# 2HE2E_Tester.net
KiCad netlist of a schematic drawn in Altium Designer
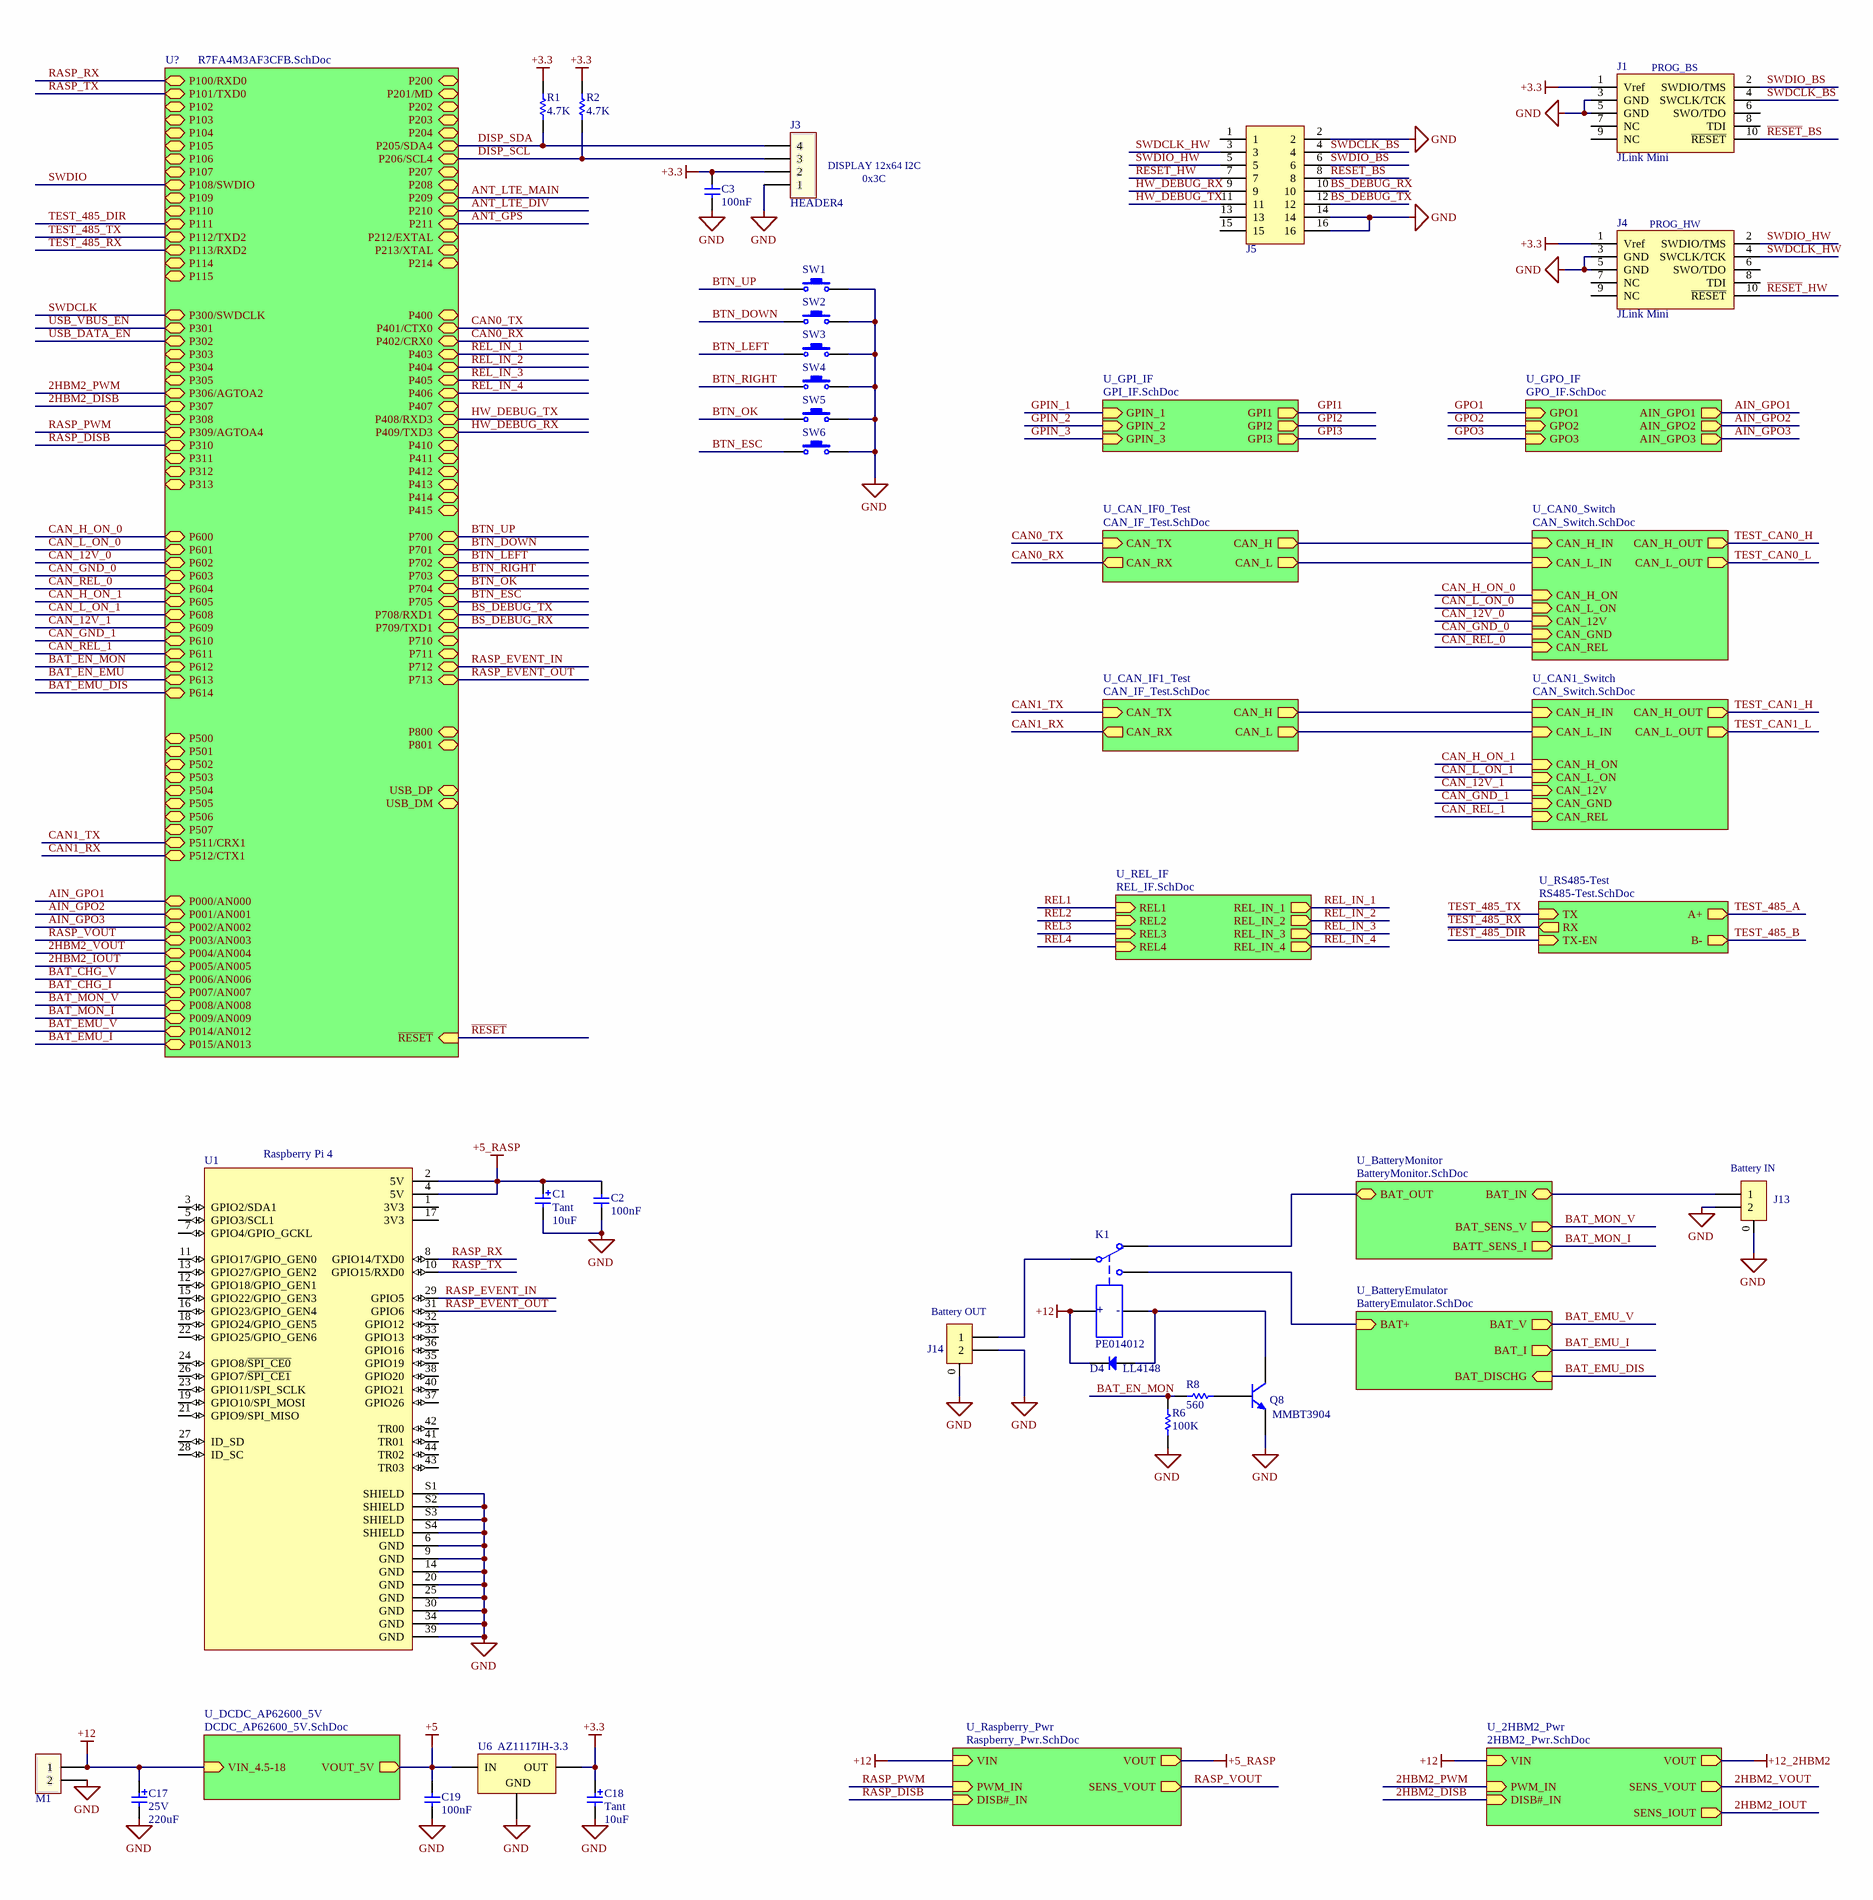
[diagram p0: 2HE2E_Tester.SchDoc, left]
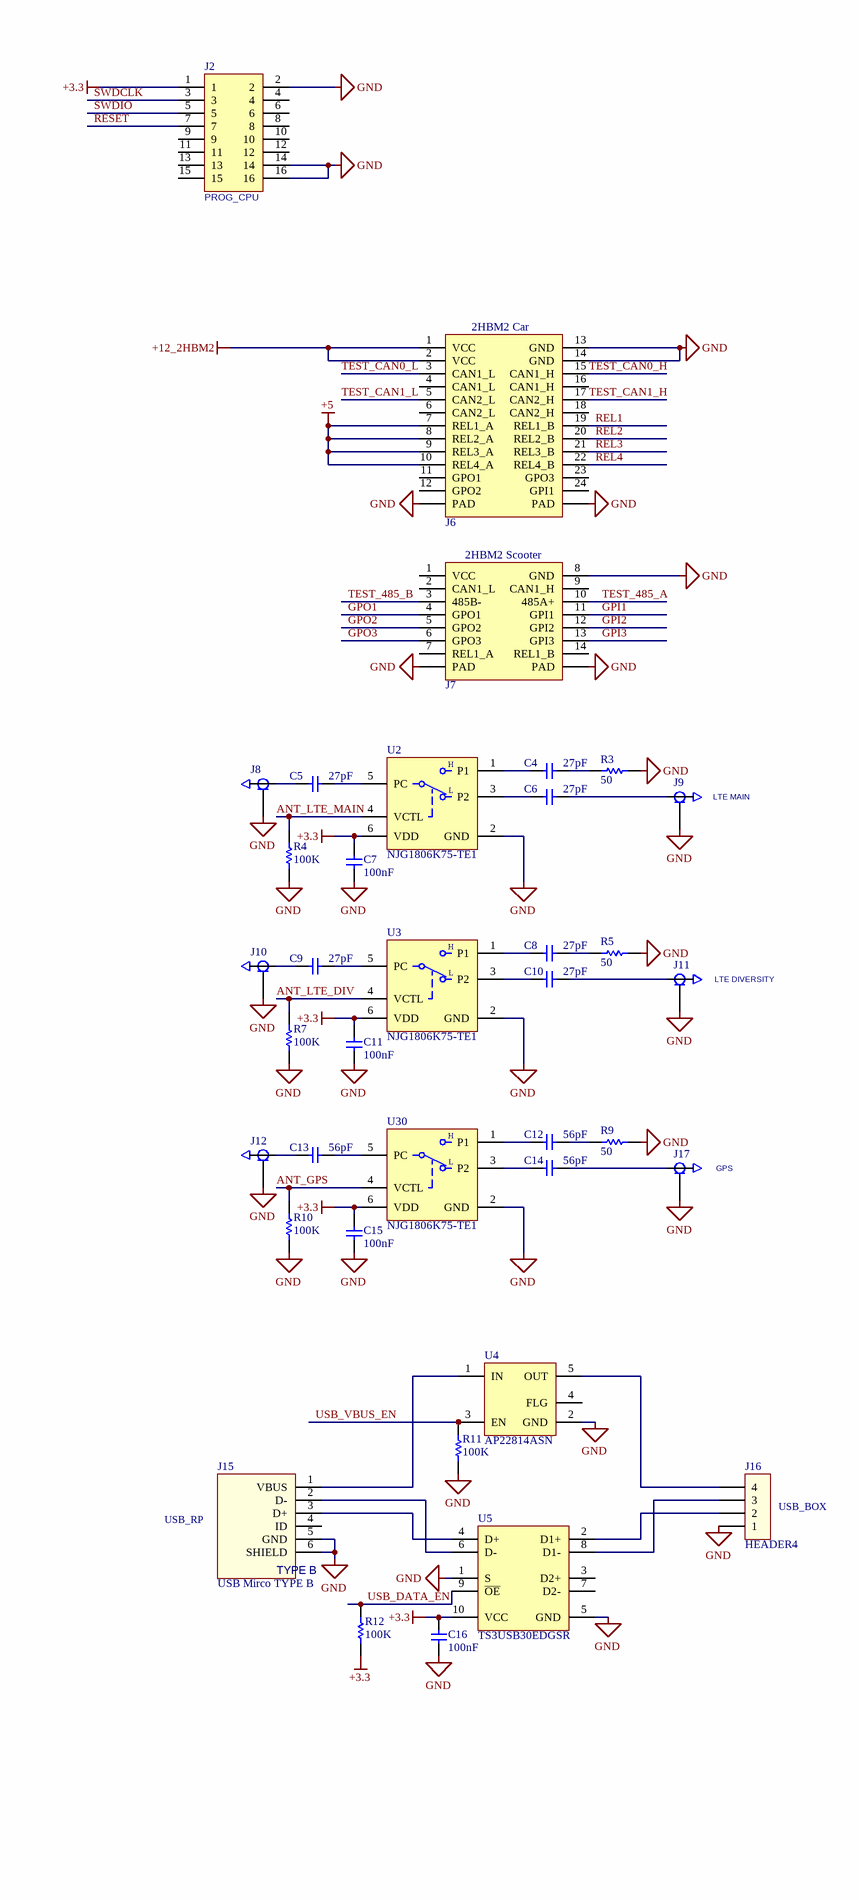
[diagram p1: 2HE2E_Tester.SchDoc, right]

(export (version "E")
  (design (tool "Eeschema 10.0.6"))
  (components
    (comp (ref "C1")
      (value "Tant")
      (footprint "Cap CASE B")
      (description "Capacitor tantalio SMD")
      (fields (field (name "ALTIUM_VALUE") "10uF"))
      (libsource (lib "Plume") (part "Cap Tantalio"))
    )
    (comp (ref "C2")
      (value "100nF")
      (footprint "0603M-C")
      (description "Ceramic Capacitor")
      (fields (field (name "Comment") "Cap Ceramic"))
      (libsource (lib "Plume") (part "Cap Ceramic"))
    )
    (comp (ref "C3")
      (value "100nF")
      (footprint "0603M-C")
      (description "Ceramic Capacitor")
      (fields (field (name "Comment") "Cap Ceramic"))
      (libsource (lib "Plume") (part "Cap Ceramic"))
    )
    (comp (ref "C4")
      (value "27pF")
      (footprint "0402M-C")
      (description "Ceramic Capacitor")
      (fields (field (name "Comment") "Cap Ceramic"))
      (libsource (lib "Plume") (part "Cap Ceramic"))
    )
    (comp (ref "C5")
      (value "27pF")
      (footprint "0402M-C")
      (description "Ceramic Capacitor")
      (fields (field (name "Comment") "Cap Ceramic"))
      (libsource (lib "Plume") (part "Cap Ceramic"))
    )
    (comp (ref "C6")
      (value "27pF")
      (footprint "0402M-C")
      (description "Ceramic Capacitor")
      (fields (field (name "Comment") "Cap Ceramic"))
      (libsource (lib "Plume") (part "Cap Ceramic"))
    )
    (comp (ref "C7")
      (value "100nF")
      (footprint "0603M-C")
      (description "Ceramic Capacitor")
      (fields (field (name "Comment") "Cap Ceramic"))
      (libsource (lib "Plume") (part "Cap Ceramic"))
    )
    (comp (ref "C8")
      (value "27pF")
      (footprint "0402M-C")
      (description "Ceramic Capacitor")
      (fields (field (name "Comment") "Cap Ceramic"))
      (libsource (lib "Plume") (part "Cap Ceramic"))
    )
    (comp (ref "C9")
      (value "27pF")
      (footprint "0402M-C")
      (description "Ceramic Capacitor")
      (fields (field (name "Comment") "Cap Ceramic"))
      (libsource (lib "Plume") (part "Cap Ceramic"))
    )
    (comp (ref "C10")
      (value "27pF")
      (footprint "0402M-C")
      (description "Ceramic Capacitor")
      (fields (field (name "Comment") "Cap Ceramic"))
      (libsource (lib "Plume") (part "Cap Ceramic"))
    )
    (comp (ref "C11")
      (value "100nF")
      (footprint "0603M-C")
      (description "Ceramic Capacitor")
      (fields (field (name "Comment") "Cap Ceramic"))
      (libsource (lib "Plume") (part "Cap Ceramic"))
    )
    (comp (ref "C12")
      (value "56pF")
      (footprint "0402M-C")
      (description "Ceramic Capacitor")
      (fields (field (name "Comment") "Cap Ceramic"))
      (libsource (lib "Plume") (part "Cap Ceramic"))
    )
    (comp (ref "C13")
      (value "56pF")
      (footprint "0402M-C")
      (description "Ceramic Capacitor")
      (fields (field (name "Comment") "Cap Ceramic"))
      (libsource (lib "Plume") (part "Cap Ceramic"))
    )
    (comp (ref "C14")
      (value "56pF")
      (footprint "0402M-C")
      (description "Ceramic Capacitor")
      (fields (field (name "Comment") "Cap Ceramic"))
      (libsource (lib "Plume") (part "Cap Ceramic"))
    )
    (comp (ref "C15")
      (value "100nF")
      (footprint "0603M-C")
      (description "Ceramic Capacitor")
      (fields (field (name "Comment") "Cap Ceramic"))
      (libsource (lib "Plume") (part "Cap Ceramic"))
    )
    (comp (ref "C16")
      (value "100nF")
      (footprint "0603M-C")
      (description "Ceramic Capacitor")
      (fields (field (name "Comment") "Cap Ceramic"))
      (libsource (lib "Plume") (part "Cap Ceramic"))
    )
    (comp (ref "C17")
      (value "25V")
      (footprint "Cap Elet SMD 8.0 mm CASE F-H10.5mm")
      (description "Condensatore elettrolitico")
      (fields (field (name "ALTIUM_VALUE") "220uF"))
      (libsource (lib "Plume") (part "Cap Elettrolitico"))
    )
    (comp (ref "C18")
      (value "Tant")
      (footprint "Cap CASE B")
      (description "Capacitor tantalio SMD")
      (fields (field (name "ALTIUM_VALUE") "10uF"))
      (libsource (lib "Plume") (part "Cap Tantalio"))
    )
    (comp (ref "C19")
      (value "100nF")
      (footprint "0603M-C")
      (description "Ceramic Capacitor")
      (fields (field (name "Comment") "Cap Ceramic"))
      (libsource (lib "Plume") (part "Cap Ceramic"))
    )
    (comp (ref "D4")
      (value "LL4148")
      (footprint "SOD80")
      (description "Small Signal Diode")
      (libsource (lib "Plume") (part "Diodo"))
    )
    (comp (ref "J1")
      (value "JLink Mini")
      (footprint "HEADER5x2-127")
      (description "Connettore JTAG/SWD 5x2 P1.27 JLink Mini")
      (libsource (lib "Plume") (part "Connettore JLink Mini"))
    )
    (comp (ref "J2")
      (value "Header 8x2")
      (footprint "Header 8x2 WE62101621021")
      (description "WE 62101621021")
      (libsource (lib "Plume") (part "Header 8x2"))
    )
    (comp (ref "J3")
      (value "HEADER4")
      (footprint "HEADER4")
      (description "Header 4 pin")
      (libsource (lib "Plume") (part "HEADER4"))
    )
    (comp (ref "J4")
      (value "JLink Mini")
      (footprint "HEADER5x2-127")
      (description "Connettore JTAG/SWD 5x2 P1.27 JLink Mini")
      (libsource (lib "Plume") (part "Connettore JLink Mini"))
    )
    (comp (ref "J5")
      (value "Header 8x2")
      (footprint "Header 8x2 WE62101621021")
      (description "WE 62101621021")
      (libsource (lib "Plume") (part "Header 8x2"))
    )
    (comp (ref "J6")
      (value "2HBM2 Car")
      (footprint "WR-MPC3 24N 662024231722")
      (description "Connettore 12x2 WE 662024231722")
      (libsource (lib "Plume") (part "Connettore 2Hire 2HBM2_Car"))
    )
    (comp (ref "J7")
      (value "2HBM2 Scooter")
      (footprint "WR-MPC3 14N 662014231722")
      (description "Connettore 7x2 WE 662014231722")
      (libsource (lib "Plume") (part "Connettore 2Hire 2HBM2_Scooter"))
    )
    (comp (ref "J8")
      (value "Antenna Ipex MHFx")
      (footprint "COAX IPEX MHF1_20279-001E-03")
      (fields (field (name "MP") "20449-001E-03") (field (name "MF") "I-PEX"))
      (libsource (lib "Plume") (part "Connettore Ipex MHFx"))
    )
    (comp (ref "J9")
      (value "Antenna Ipex MHFx")
      (footprint "COAX IPEX MHF1_20279-001E-03")
      (fields (field (name "MP") "20449-001E-03") (field (name "MF") "I-PEX"))
      (libsource (lib "Plume") (part "Connettore Ipex MHFx"))
    )
    (comp (ref "J10")
      (value "Antenna Ipex MHFx")
      (footprint "COAX IPEX MHF1_20279-001E-03")
      (fields (field (name "MP") "20449-001E-03") (field (name "MF") "I-PEX"))
      (libsource (lib "Plume") (part "Connettore Ipex MHFx"))
    )
    (comp (ref "J11")
      (value "Antenna Ipex MHFx")
      (footprint "COAX IPEX MHF1_20279-001E-03")
      (fields (field (name "MP") "20449-001E-03") (field (name "MF") "I-PEX"))
      (libsource (lib "Plume") (part "Connettore Ipex MHFx"))
    )
    (comp (ref "J12")
      (value "Antenna Ipex MHFx")
      (footprint "COAX IPEX MHF1_20279-001E-03")
      (fields (field (name "MP") "20449-001E-03") (field (name "MF") "I-PEX"))
      (libsource (lib "Plume") (part "Connettore Ipex MHFx"))
    )
    (comp (ref "J13")
      (value "Connettore 2x1+GND")
      (footprint "JST_S2B-PH-SM4-TB")
      (description "Connettore 2x1")
      (libsource (lib "Plume") (part "Connettore 2x1+GND"))
    )
    (comp (ref "J14")
      (value "Connettore 2x1+GND")
      (footprint "JST_S2B-PH-SM4-TB")
      (description "Connettore 2x1")
      (libsource (lib "") (part "Connettore 2x1+GND_1"))
    )
    (comp (ref "J15")
      (value "USB Mirco TYPE B")
      (footprint "USB Micro Type B - WE629105136821")
      (description "Connettore MicroUSB Client (TYPE B)")
      (libsource (lib "Plume") (part "USB Micro_TYPEB"))
    )
    (comp (ref "J16")
      (value "HEADER4")
      (footprint "HEADER4")
      (description "Header 4 pin")
      (libsource (lib "Plume") (part "HEADER4"))
    )
    (comp (ref "J17")
      (value "Antenna Ipex MHFx")
      (footprint "COAX IPEX MHF1_20279-001E-03")
      (fields (field (name "MP") "20449-001E-03") (field (name "MF") "I-PEX"))
      (libsource (lib "Plume") (part "Connettore Ipex MHFx"))
    )
    (comp (ref "K1")
      (value "PE014012")
      (footprint "Relay PE")
      (description "Relay DPDT Coil 12V PE014012")
      (libsource (lib "Plume") (part "Relay SPDT"))
    )
    (comp (ref "M1")
      (value "Morsetto 2 Poli")
      (footprint "Morsetto-2 poli-5.08")
      (description "Morsetto 2 poli PCB")
      (libsource (lib "Plume") (part "Morsetto 2 Poli"))
    )
    (comp (ref "Q8")
      (value "MMBT3904")
      (footprint "SOT23 BSR14")
      (description "NPN Bipolar Transistor")
      (libsource (lib "Plume") (part "Transistor NPN"))
    )
    (comp (ref "R1")
      (value "4.7K")
      (footprint "0603M")
      (description "Resistor")
      (libsource (lib "Plume") (part "Resistor"))
    )
    (comp (ref "R2")
      (value "4.7K")
      (footprint "0603M")
      (description "Resistor")
      (libsource (lib "Plume") (part "Resistor"))
    )
    (comp (ref "R3")
      (value "50")
      (footprint "0603M")
      (description "Resistor")
      (libsource (lib "Plume") (part "Resistor"))
    )
    (comp (ref "R4")
      (value "100K")
      (footprint "0603M")
      (description "Resistor")
      (libsource (lib "Plume") (part "Resistor"))
    )
    (comp (ref "R5")
      (value "50")
      (footprint "0603M")
      (description "Resistor")
      (libsource (lib "Plume") (part "Resistor"))
    )
    (comp (ref "R6")
      (value "100K")
      (footprint "0603M")
      (description "Resistor")
      (libsource (lib "Plume") (part "Resistor"))
    )
    (comp (ref "R7")
      (value "100K")
      (footprint "0603M")
      (description "Resistor")
      (libsource (lib "Plume") (part "Resistor"))
    )
    (comp (ref "R8")
      (value "560")
      (footprint "0603M")
      (description "Resistor")
      (libsource (lib "Plume") (part "Resistor"))
    )
    (comp (ref "R9")
      (value "50")
      (footprint "0603M")
      (description "Resistor")
      (libsource (lib "Plume") (part "Resistor"))
    )
    (comp (ref "R10")
      (value "100K")
      (footprint "0603M")
      (description "Resistor")
      (libsource (lib "Plume") (part "Resistor"))
    )
    (comp (ref "R11")
      (value "100K")
      (footprint "0603M")
      (description "Resistor")
      (libsource (lib "Plume") (part "Resistor"))
    )
    (comp (ref "R12")
      (value "100K")
      (footprint "0603M")
      (description "Resistor")
      (libsource (lib "Plume") (part "Resistor"))
    )
    (comp (ref "SW1")
      (value "Button")
      (footprint "Button 6x6 PHT")
      (description "Button SPST")
      (libsource (lib "Plume") (part "Button"))
    )
    (comp (ref "SW2")
      (value "Button")
      (footprint "Button 6x6 PHT")
      (description "Button SPST")
      (libsource (lib "Plume") (part "Button"))
    )
    (comp (ref "SW3")
      (value "Button")
      (footprint "Button 6x6 PHT")
      (description "Button SPST")
      (libsource (lib "Plume") (part "Button"))
    )
    (comp (ref "SW4")
      (value "Button")
      (footprint "Button 6x6 PHT")
      (description "Button SPST")
      (libsource (lib "Plume") (part "Button"))
    )
    (comp (ref "SW5")
      (value "Button")
      (footprint "Button 6x6 PHT")
      (description "Button SPST")
      (libsource (lib "Plume") (part "Button"))
    )
    (comp (ref "SW6")
      (value "Button")
      (footprint "Button 6x6 PHT")
      (description "Button SPST")
      (libsource (lib "Plume") (part "Button"))
    )
    (comp (ref "U1")
      (value "Raspberry Pi 4")
      (footprint "MODULE RASPBERRY PI 4B")
      (description "BCM2711 Raspberry Pi 4 Model B 4GB - ARM Cortex-A72 MPU Embedded Evaluation Board")
      (fields (field (name "MF") "Raspberry Pi") (field (name "MP") "RASPBERRY PI 4B/4GB"))
      (libsource (lib "Plume") (part "Raspberry Pi 4"))
    )
    (comp (ref "U2")
      (value "NJG1806K75-TE1")
      (footprint "NJG1806K75TE1")
      (description "RF Switch ICs 1bit SPDT Switch IC GaAs MMIC")
      (libsource (lib "Plume") (part "NJG1806K75-TE1"))
    )
    (comp (ref "U3")
      (value "NJG1806K75-TE1")
      (footprint "NJG1806K75TE1")
      (description "RF Switch ICs 1bit SPDT Switch IC GaAs MMIC")
      (libsource (lib "Plume") (part "NJG1806K75-TE1"))
    )
    (comp (ref "U4")
      (value "AP22814ASN")
      (footprint "U-DFN2020-127P600-6N")
      (description "Single  channel current-limited  integrated high-side power switch - Active High - DFN")
      (libsource (lib "Plume") (part "AP22814ASN"))
    )
    (comp (ref "U5")
      (value "TS3USB30EDGSR")
      (footprint "TSSOP50P491-10N")
      (description "High-Speed USB 2.0 (480-Mbps) 1:2 Multiplexer/Demultiplexer Switch With Single Enable")
      (libsource (lib "Plume") (part "TS3USB30EDGSR"))
    )
    (comp (ref "U6")
      (value "AZ1117IH-3.3")
      (footprint "SOT223-SOT230P700X180-4N")
      (description "Regolatore LDO fixed 3.3V 1A")
      (libsource (lib "Plume") (part "AZ1117IH"))
    )
    (comp (ref "U30")
      (value "NJG1806K75-TE1")
      (footprint "NJG1806K75TE1")
      (description "RF Switch ICs 1bit SPDT Switch IC GaAs MMIC")
      (libsource (lib "Plume") (part "NJG1806K75-TE1"))
    )
  )
  (nets
    (net (code "1") (name "+3.3") (class "Default")
      (node (ref "C11") (pin "1") (pinfunction "1_1") (pintype "passive"))
      (node (ref "C15") (pin "1") (pinfunction "1_1") (pintype "passive"))
      (node (ref "C16") (pin "1") (pinfunction "1_1") (pintype "passive"))
      (node (ref "C18") (pin "1") (pinfunction "1_1") (pintype "passive"))
      (node (ref "C3") (pin "1") (pinfunction "1_1") (pintype "passive"))
      (node (ref "C7") (pin "1") (pinfunction "1_1") (pintype "passive"))
      (node (ref "J1") (pin "1") (pinfunction "Vref_1") (pintype "passive"))
      (node (ref "J2") (pin "1") (pinfunction "1_1") (pintype "passive"))
      (node (ref "J3") (pin "2") (pinfunction "2_2") (pintype "passive"))
      (node (ref "J4") (pin "1") (pinfunction "Vref_1") (pintype "passive"))
      (node (ref "R1") (pin "2") (pinfunction "2_2") (pintype "passive"))
      (node (ref "R12") (pin "1") (pinfunction "1_1") (pintype "passive"))
      (node (ref "R2") (pin "2") (pinfunction "2_2") (pintype "passive"))
      (node (ref "U2") (pin "6") (pinfunction "VDD_6") (pintype "passive"))
      (node (ref "U3") (pin "6") (pinfunction "VDD_6") (pintype "passive"))
      (node (ref "U30") (pin "6") (pinfunction "VDD_6") (pintype "passive"))
      (node (ref "U5") (pin "10") (pinfunction "VCC_10") (pintype "passive"))
      (node (ref "U6") (pin "2") (pinfunction "OUT_2") (pintype "passive"))
    )
    (net (code "2") (name "+5") (class "Default")
      (node (ref "C19") (pin "1") (pinfunction "1_1") (pintype "passive"))
      (node (ref "J6") (pin "10") (pinfunction "REL4_A_10") (pintype "passive"))
      (node (ref "J6") (pin "7") (pinfunction "REL1_A_7") (pintype "passive"))
      (node (ref "J6") (pin "8") (pinfunction "REL2_A_8") (pintype "passive"))
      (node (ref "J6") (pin "9") (pinfunction "REL3_A_9") (pintype "passive"))
      (node (ref "U6") (pin "3") (pinfunction "IN_3") (pintype "passive"))
    )
    (net (code "3") (name "+5_RASP") (class "Default")
      (node (ref "C1") (pin "1") (pinfunction "1_1") (pintype "passive"))
      (node (ref "C2") (pin "1") (pinfunction "1_1") (pintype "passive"))
      (node (ref "U1") (pin "2") (pinfunction "5V_2") (pintype "power_in"))
      (node (ref "U1") (pin "4") (pinfunction "5V_4") (pintype "power_in"))
    )
    (net (code "4") (name "+12") (class "Default")
      (node (ref "C17") (pin "1") (pinfunction "1_1") (pintype "passive"))
      (node (ref "D4") (pin "2") (pinfunction "K_2") (pintype "passive"))
      (node (ref "K1") (pin "1") (pinfunction "1_1") (pintype "passive"))
      (node (ref "M1") (pin "1") (pinfunction "1_1") (pintype "passive"))
    )
    (net (code "5") (name "+12_2HBM2") (class "Default")
      (node (ref "J6") (pin "1") (pinfunction "VCC_1") (pintype "passive"))
      (node (ref "J6") (pin "2") (pinfunction "VCC_2") (pintype "passive"))
    )
    (net (code "13") (name "/ANT_GPS") (class "Default")
      (node (ref "R10") (pin "2") (pinfunction "2_2") (pintype "passive"))
      (node (ref "U30") (pin "4") (pinfunction "VCTL_4") (pintype "passive"))
    )
    (net (code "14") (name "/ANT_LTE_DIV") (class "Default")
      (node (ref "R7") (pin "2") (pinfunction "2_2") (pintype "passive"))
      (node (ref "U3") (pin "4") (pinfunction "VCTL_4") (pintype "passive"))
    )
    (net (code "15") (name "/ANT_LTE_MAIN") (class "Default")
      (node (ref "R4") (pin "2") (pinfunction "2_2") (pintype "passive"))
      (node (ref "U2") (pin "4") (pinfunction "VCTL_4") (pintype "passive"))
    )
    (net (code "16") (name "/BAT+") (class "Default")
      (node (ref "K1") (pin "12") (pinfunction "12_12") (pintype "passive"))
    )
    (net (code "23") (name "/BAT_EN_MON") (class "Default")
      (node (ref "R6") (pin "1") (pinfunction "1_1") (pintype "passive"))
      (node (ref "R8") (pin "1") (pinfunction "1_1") (pintype "passive"))
    )
    (net (code "24") (name "/BAT_IN") (class "Default")
      (node (ref "J13") (pin "1") (pinfunction "1_1") (pintype "passive"))
    )
    (net (code "27") (name "/BAT_OUT") (class "Default")
      (node (ref "K1") (pin "10") (pinfunction "10_10") (pintype "passive"))
    )
    (net (code "28") (name "/BS_DEBUG_RX") (class "Default")
      (node (ref "J5") (pin "10") (pinfunction "10_10") (pintype "passive"))
    )
    (net (code "29") (name "/BS_DEBUG_TX") (class "Default")
      (node (ref "J5") (pin "12") (pinfunction "12_12") (pintype "passive"))
    )
    (net (code "30") (name "/BTN_DOWN") (class "Default")
      (node (ref "SW2") (pin "1") (pinfunction "1_1") (pintype "passive"))
    )
    (net (code "31") (name "/BTN_ESC") (class "Default")
      (node (ref "SW6") (pin "1") (pinfunction "1_1") (pintype "passive"))
    )
    (net (code "32") (name "/BTN_LEFT") (class "Default")
      (node (ref "SW3") (pin "1") (pinfunction "1_1") (pintype "passive"))
    )
    (net (code "33") (name "/BTN_OK") (class "Default")
      (node (ref "SW5") (pin "1") (pinfunction "1_1") (pintype "passive"))
    )
    (net (code "34") (name "/BTN_RIGHT") (class "Default")
      (node (ref "SW4") (pin "1") (pinfunction "1_1") (pintype "passive"))
    )
    (net (code "35") (name "/BTN_UP") (class "Default")
      (node (ref "SW1") (pin "1") (pinfunction "1_1") (pintype "passive"))
    )
    (net (code "54") (name "/DISP_SCL") (class "Default")
      (node (ref "J3") (pin "3") (pinfunction "3_3") (pintype "passive"))
      (node (ref "R2") (pin "1") (pinfunction "1_1") (pintype "passive"))
    )
    (net (code "55") (name "/DISP_SDA") (class "Default")
      (node (ref "J3") (pin "4") (pinfunction "4_4") (pintype "passive"))
      (node (ref "R1") (pin "1") (pinfunction "1_1") (pintype "passive"))
    )
    (net (code "56") (name "/GPI1") (class "Default")
      (node (ref "J7") (pin "11") (pinfunction "GPI1_11") (pintype "passive"))
    )
    (net (code "57") (name "/GPI2") (class "Default")
      (node (ref "J7") (pin "12") (pinfunction "GPI2_12") (pintype "passive"))
    )
    (net (code "58") (name "/GPI3") (class "Default")
      (node (ref "J7") (pin "13") (pinfunction "GPI3_13") (pintype "passive"))
    )
    (net (code "62") (name "/GPO1") (class "Default")
      (node (ref "J7") (pin "4") (pinfunction "GPO1_4") (pintype "passive"))
    )
    (net (code "63") (name "/GPO2") (class "Default")
      (node (ref "J7") (pin "5") (pinfunction "GPO2_5") (pintype "passive"))
    )
    (net (code "64") (name "/GPO3") (class "Default")
      (node (ref "J7") (pin "6") (pinfunction "GPO3_6") (pintype "passive"))
    )
    (net (code "65") (name "/HW_DEBUG_RX") (class "Default")
      (node (ref "J5") (pin "9") (pinfunction "9_9") (pintype "passive"))
    )
    (net (code "66") (name "/HW_DEBUG_TX") (class "Default")
      (node (ref "J5") (pin "11") (pinfunction "11_11") (pintype "passive"))
    )
    (net (code "115") (name "/RASP_EVENT_IN") (class "Default")
      (node (ref "U1") (pin "29") (pinfunction "GPIO5_29") (pintype "bidirectional"))
    )
    (net (code "116") (name "/RASP_EVENT_OUT") (class "Default")
      (node (ref "U1") (pin "31") (pinfunction "GPIO6_31") (pintype "bidirectional"))
    )
    (net (code "118") (name "/RASP_RX") (class "Default")
      (node (ref "U1") (pin "8") (pinfunction "GPIO14/TXD0_8") (pintype "bidirectional"))
    )
    (net (code "119") (name "/RASP_TX") (class "Default")
      (node (ref "U1") (pin "10") (pinfunction "GPIO15/RXD0_10") (pintype "bidirectional"))
    )
    (net (code "121") (name "/REL1") (class "Default")
      (node (ref "J6") (pin "19") (pinfunction "REL1_B_19") (pintype "passive"))
    )
    (net (code "122") (name "/REL2") (class "Default")
      (node (ref "J6") (pin "20") (pinfunction "REL2_B_20") (pintype "passive"))
    )
    (net (code "123") (name "/REL3") (class "Default")
      (node (ref "J6") (pin "21") (pinfunction "REL3_B_21") (pintype "passive"))
    )
    (net (code "124") (name "/REL4") (class "Default")
      (node (ref "J6") (pin "22") (pinfunction "REL4_B_22") (pintype "passive"))
    )
    (net (code "129") (name "/SWDCLK") (class "Default")
      (node (ref "J2") (pin "3") (pinfunction "3_3") (pintype "passive"))
    )
    (net (code "130") (name "/SWDCLK_BS") (class "Default")
      (node (ref "J1") (pin "4") (pinfunction "SWCLK/TCK_4") (pintype "passive"))
      (node (ref "J5") (pin "4") (pinfunction "4_4") (pintype "passive"))
    )
    (net (code "131") (name "/SWDCLK_HW") (class "Default")
      (node (ref "J4") (pin "4") (pinfunction "SWCLK/TCK_4") (pintype "passive"))
      (node (ref "J5") (pin "3") (pinfunction "3_3") (pintype "passive"))
    )
    (net (code "132") (name "/SWDIO") (class "Default")
      (node (ref "J2") (pin "5") (pinfunction "5_5") (pintype "passive"))
    )
    (net (code "133") (name "/SWDIO_BS") (class "Default")
      (node (ref "J1") (pin "2") (pinfunction "SWDIO/TMS_2") (pintype "passive"))
      (node (ref "J5") (pin "6") (pinfunction "6_6") (pintype "passive"))
    )
    (net (code "134") (name "/SWDIO_HW") (class "Default")
      (node (ref "J4") (pin "2") (pinfunction "SWDIO/TMS_2") (pintype "passive"))
      (node (ref "J5") (pin "5") (pinfunction "5_5") (pintype "passive"))
    )
    (net (code "135") (name "/TEST_485_A") (class "Default")
      (node (ref "J7") (pin "10") (pinfunction "485A+_10") (pintype "passive"))
    )
    (net (code "136") (name "/TEST_485_B") (class "Default")
      (node (ref "J7") (pin "3") (pinfunction "485B-_3") (pintype "passive"))
    )
    (net (code "140") (name "/TEST_CAN0_H") (class "Default")
      (node (ref "J6") (pin "15") (pinfunction "CAN1_H_15") (pintype "passive"))
    )
    (net (code "141") (name "/TEST_CAN0_L") (class "Default")
      (node (ref "J6") (pin "3") (pinfunction "CAN1_L_3") (pintype "passive"))
    )
    (net (code "142") (name "/TEST_CAN1_H") (class "Default")
      (node (ref "J6") (pin "17") (pinfunction "CAN2_H_17") (pintype "passive"))
    )
    (net (code "143") (name "/TEST_CAN1_L") (class "Default")
      (node (ref "J6") (pin "5") (pinfunction "CAN2_L_5") (pintype "passive"))
    )
    (net (code "144") (name "/USB_DATA_EN") (class "Default")
      (node (ref "R12") (pin "2") (pinfunction "2_2") (pintype "passive"))
      (node (ref "U5") (pin "9") (pinfunction "~{OE}_9") (pintype "passive"))
    )
    (net (code "147") (name "/USB_VBUS_EN") (class "Default")
      (node (ref "R11") (pin "2") (pinfunction "2_2") (pintype "passive"))
      (node (ref "U4") (pin "3") (pinfunction "EN_3") (pintype "passive"))
    )
    (net (code "148") (name "/~{RESET}") (class "Default")
      (node (ref "J2") (pin "7") (pinfunction "7_7") (pintype "passive"))
    )
    (net (code "149") (name "/~{RESET}_BS") (class "Default")
      (node (ref "J1") (pin "10") (pinfunction "~{RESET}_10") (pintype "passive"))
      (node (ref "J5") (pin "8") (pinfunction "8_8") (pintype "passive"))
    )
    (net (code "150") (name "/~{RESET}_HW") (class "Default")
      (node (ref "J4") (pin "10") (pinfunction "~{RESET}_10") (pintype "passive"))
      (node (ref "J5") (pin "7") (pinfunction "7_7") (pintype "passive"))
    )
    (net (code "151") (name "GND") (class "Default")
      (node (ref "C1") (pin "2") (pinfunction "2_2") (pintype "passive"))
      (node (ref "C11") (pin "2") (pinfunction "2_2") (pintype "passive"))
      (node (ref "C15") (pin "2") (pinfunction "2_2") (pintype "passive"))
      (node (ref "C16") (pin "2") (pinfunction "2_2") (pintype "passive"))
      (node (ref "C17") (pin "2") (pinfunction "2_2") (pintype "passive"))
      (node (ref "C18") (pin "2") (pinfunction "2_2") (pintype "passive"))
      (node (ref "C19") (pin "2") (pinfunction "2_2") (pintype "passive"))
      (node (ref "C2") (pin "2") (pinfunction "2_2") (pintype "passive"))
      (node (ref "C3") (pin "2") (pinfunction "2_2") (pintype "passive"))
      (node (ref "C7") (pin "2") (pinfunction "2_2") (pintype "passive"))
      (node (ref "J1") (pin "3") (pinfunction "GND_3") (pintype "passive"))
      (node (ref "J1") (pin "5") (pinfunction "GND_5") (pintype "passive"))
      (node (ref "J10") (pin "2") (pinfunction "GND_2") (pintype "power_in"))
      (node (ref "J11") (pin "2") (pinfunction "GND_2") (pintype "power_in"))
      (node (ref "J12") (pin "2") (pinfunction "GND_2") (pintype "power_in"))
      (node (ref "J13") (pin "0") (pinfunction "0_0") (pintype "passive"))
      (node (ref "J13") (pin "2") (pinfunction "2_2") (pintype "passive"))
      (node (ref "J14") (pin "0") (pinfunction "0_0") (pintype "passive"))
      (node (ref "J14") (pin "2") (pinfunction "2_2") (pintype "passive"))
      (node (ref "J15") (pin "5") (pinfunction "GND_5") (pintype "passive"))
      (node (ref "J15") (pin "6") (pinfunction "SHIELD_6") (pintype "passive"))
      (node (ref "J16") (pin "1") (pinfunction "1_1") (pintype "passive"))
      (node (ref "J17") (pin "2") (pinfunction "GND_2") (pintype "power_in"))
      (node (ref "J2") (pin "14") (pinfunction "14_14") (pintype "passive"))
      (node (ref "J2") (pin "16") (pinfunction "16_16") (pintype "passive"))
      (node (ref "J2") (pin "2") (pinfunction "2_2") (pintype "passive"))
      (node (ref "J3") (pin "1") (pinfunction "1_1") (pintype "passive"))
      (node (ref "J4") (pin "3") (pinfunction "GND_3") (pintype "passive"))
      (node (ref "J4") (pin "5") (pinfunction "GND_5") (pintype "passive"))
      (node (ref "J5") (pin "14") (pinfunction "14_14") (pintype "passive"))
      (node (ref "J5") (pin "16") (pinfunction "16_16") (pintype "passive"))
      (node (ref "J5") (pin "2") (pinfunction "2_2") (pintype "passive"))
      (node (ref "J6") (pin "13") (pinfunction "GND_13") (pintype "passive"))
      (node (ref "J6") (pin "14") (pinfunction "GND_14") (pintype "passive"))
      (node (ref "J6") (pin "MP1") (pinfunction "PAD_MP1") (pintype "passive"))
      (node (ref "J6") (pin "MP2") (pinfunction "PAD_MP2") (pintype "passive"))
      (node (ref "J7") (pin "8") (pinfunction "GND_8") (pintype "passive"))
      (node (ref "J7") (pin "MP1") (pinfunction "PAD_MP1") (pintype "passive"))
      (node (ref "J7") (pin "MP2") (pinfunction "PAD_MP2") (pintype "passive"))
      (node (ref "J8") (pin "2") (pinfunction "GND_2") (pintype "power_in"))
      (node (ref "J9") (pin "2") (pinfunction "GND_2") (pintype "power_in"))
      (node (ref "M1") (pin "2") (pinfunction "2_2") (pintype "passive"))
      (node (ref "Q8") (pin "3") (pinfunction "E_3") (pintype "passive"))
      (node (ref "R10") (pin "1") (pinfunction "1_1") (pintype "passive"))
      (node (ref "R11") (pin "1") (pinfunction "1_1") (pintype "passive"))
      (node (ref "R3") (pin "1") (pinfunction "1_1") (pintype "passive"))
      (node (ref "R4") (pin "1") (pinfunction "1_1") (pintype "passive"))
      (node (ref "R5") (pin "1") (pinfunction "1_1") (pintype "passive"))
      (node (ref "R6") (pin "2") (pinfunction "2_2") (pintype "passive"))
      (node (ref "R7") (pin "1") (pinfunction "1_1") (pintype "passive"))
      (node (ref "R9") (pin "1") (pinfunction "1_1") (pintype "passive"))
      (node (ref "SW1") (pin "2") (pinfunction "2_2") (pintype "passive"))
      (node (ref "SW2") (pin "2") (pinfunction "2_2") (pintype "passive"))
      (node (ref "SW3") (pin "2") (pinfunction "2_2") (pintype "passive"))
      (node (ref "SW4") (pin "2") (pinfunction "2_2") (pintype "passive"))
      (node (ref "SW5") (pin "2") (pinfunction "2_2") (pintype "passive"))
      (node (ref "SW6") (pin "2") (pinfunction "2_2") (pintype "passive"))
      (node (ref "U1") (pin "14") (pinfunction "GND_14") (pintype "power_in"))
      (node (ref "U1") (pin "20") (pinfunction "GND_20") (pintype "power_in"))
      (node (ref "U1") (pin "25") (pinfunction "GND_25") (pintype "power_in"))
      (node (ref "U1") (pin "30") (pinfunction "GND_30") (pintype "power_in"))
      (node (ref "U1") (pin "34") (pinfunction "GND_34") (pintype "power_in"))
      (node (ref "U1") (pin "39") (pinfunction "GND_39") (pintype "power_in"))
      (node (ref "U1") (pin "6") (pinfunction "GND_6") (pintype "power_in"))
      (node (ref "U1") (pin "9") (pinfunction "GND_9") (pintype "power_in"))
      (node (ref "U1") (pin "S1") (pinfunction "SHIELD_S1") (pintype "power_in"))
      (node (ref "U1") (pin "S2") (pinfunction "SHIELD_S2") (pintype "power_in"))
      (node (ref "U1") (pin "S3") (pinfunction "SHIELD_S3") (pintype "power_in"))
      (node (ref "U1") (pin "S4") (pinfunction "SHIELD_S4") (pintype "power_in"))
      (node (ref "U2") (pin "2") (pinfunction "GND_2") (pintype "passive"))
      (node (ref "U3") (pin "2") (pinfunction "GND_2") (pintype "passive"))
      (node (ref "U30") (pin "2") (pinfunction "GND_2") (pintype "passive"))
      (node (ref "U4") (pin "2") (pinfunction "GND_2") (pintype "passive"))
      (node (ref "U5") (pin "1") (pinfunction "S_1") (pintype "passive"))
      (node (ref "U5") (pin "5") (pinfunction "GND_5") (pintype "passive"))
      (node (ref "U6") (pin "1") (pinfunction "GND_1") (pintype "passive"))
    )
    (net (code "152") (name "Net-(C4-Pad2)") (class "Default")
      (node (ref "C4") (pin "2") (pinfunction "2_2") (pintype "passive"))
      (node (ref "R3") (pin "2") (pinfunction "2_2") (pintype "passive"))
    )
    (net (code "153") (name "Net-(C8-Pad2)") (class "Default")
      (node (ref "C8") (pin "2") (pinfunction "2_2") (pintype "passive"))
      (node (ref "R5") (pin "2") (pinfunction "2_2") (pintype "passive"))
    )
    (net (code "154") (name "Net-(C12-Pad2)") (class "Default")
      (node (ref "C12") (pin "2") (pinfunction "2_2") (pintype "passive"))
      (node (ref "R9") (pin "2") (pinfunction "2_2") (pintype "passive"))
    )
    (net (code "155") (name "Net-(D4-A)") (class "Default")
      (node (ref "D4") (pin "1") (pinfunction "A_1") (pintype "passive"))
      (node (ref "K1") (pin "6") (pinfunction "6_6") (pintype "passive"))
      (node (ref "Q8") (pin "1") (pinfunction "C_1") (pintype "passive"))
    )
    (net (code "156") (name "Net-(J8-SIGNAL)") (class "Default")
      (node (ref "C5") (pin "1") (pinfunction "1_1") (pintype "passive"))
      (node (ref "J8") (pin "1") (pinfunction "SIGNAL_1") (pintype "passive"))
    )
    (net (code "157") (name "Net-(J9-SIGNAL)") (class "Default")
      (node (ref "C6") (pin "2") (pinfunction "2_2") (pintype "passive"))
      (node (ref "J9") (pin "1") (pinfunction "SIGNAL_1") (pintype "passive"))
    )
    (net (code "158") (name "Net-(J10-SIGNAL)") (class "Default")
      (node (ref "C9") (pin "1") (pinfunction "1_1") (pintype "passive"))
      (node (ref "J10") (pin "1") (pinfunction "SIGNAL_1") (pintype "passive"))
    )
    (net (code "159") (name "Net-(J11-SIGNAL)") (class "Default")
      (node (ref "C10") (pin "2") (pinfunction "2_2") (pintype "passive"))
      (node (ref "J11") (pin "1") (pinfunction "SIGNAL_1") (pintype "passive"))
    )
    (net (code "160") (name "Net-(J12-SIGNAL)") (class "Default")
      (node (ref "C13") (pin "1") (pinfunction "1_1") (pintype "passive"))
      (node (ref "J12") (pin "1") (pinfunction "SIGNAL_1") (pintype "passive"))
    )
    (net (code "161") (name "Net-(J14-Pad1)") (class "Default")
      (node (ref "J14") (pin "1") (pinfunction "1_1") (pintype "passive"))
      (node (ref "K1") (pin "7") (pinfunction "7_7") (pintype "passive"))
    )
    (net (code "162") (name "Net-(J15-D+)") (class "Default")
      (node (ref "J15") (pin "3") (pinfunction "D+_3") (pintype "passive"))
      (node (ref "U5") (pin "4") (pinfunction "D+_4") (pintype "passive"))
    )
    (net (code "163") (name "Net-(J15-D-)") (class "Default")
      (node (ref "J15") (pin "2") (pinfunction "D-_2") (pintype "passive"))
      (node (ref "U5") (pin "6") (pinfunction "D-_6") (pintype "passive"))
    )
    (net (code "164") (name "Net-(J15-VBUS)") (class "Default")
      (node (ref "J15") (pin "1") (pinfunction "VBUS_1") (pintype "passive"))
      (node (ref "U4") (pin "1") (pinfunction "IN_1") (pintype "passive"))
    )
    (net (code "165") (name "Net-(J17-SIGNAL)") (class "Default")
      (node (ref "C14") (pin "2") (pinfunction "2_2") (pintype "passive"))
      (node (ref "J17") (pin "1") (pinfunction "SIGNAL_1") (pintype "passive"))
    )
    (net (code "166") (name "Net-(Q8-B)") (class "Default")
      (node (ref "Q8") (pin "2") (pinfunction "B_2") (pintype "passive"))
      (node (ref "R8") (pin "2") (pinfunction "2_2") (pintype "passive"))
    )
    (net (code "167") (name "Net-(U2-P1)") (class "Default")
      (node (ref "C4") (pin "1") (pinfunction "1_1") (pintype "passive"))
      (node (ref "U2") (pin "1") (pinfunction "P1_1") (pintype "passive"))
    )
    (net (code "168") (name "Net-(U2-P2)") (class "Default")
      (node (ref "C6") (pin "1") (pinfunction "1_1") (pintype "passive"))
      (node (ref "U2") (pin "3") (pinfunction "P2_3") (pintype "passive"))
    )
    (net (code "169") (name "Net-(U2-PC)") (class "Default")
      (node (ref "C5") (pin "2") (pinfunction "2_2") (pintype "passive"))
      (node (ref "U2") (pin "5") (pinfunction "PC_5") (pintype "passive"))
    )
    (net (code "170") (name "Net-(U3-P1)") (class "Default")
      (node (ref "C8") (pin "1") (pinfunction "1_1") (pintype "passive"))
      (node (ref "U3") (pin "1") (pinfunction "P1_1") (pintype "passive"))
    )
    (net (code "171") (name "Net-(U3-P2)") (class "Default")
      (node (ref "C10") (pin "1") (pinfunction "1_1") (pintype "passive"))
      (node (ref "U3") (pin "3") (pinfunction "P2_3") (pintype "passive"))
    )
    (net (code "172") (name "Net-(U3-PC)") (class "Default")
      (node (ref "C9") (pin "2") (pinfunction "2_2") (pintype "passive"))
      (node (ref "U3") (pin "5") (pinfunction "PC_5") (pintype "passive"))
    )
    (net (code "173") (name "Net-(U4-OUT)") (class "Default")
      (node (ref "J16") (pin "4") (pinfunction "4_4") (pintype "passive"))
      (node (ref "U4") (pin "5") (pinfunction "OUT_5") (pintype "passive"))
    )
    (net (code "174") (name "Net-(U5-D1+)") (class "Default")
      (node (ref "J16") (pin "2") (pinfunction "2_2") (pintype "passive"))
      (node (ref "U5") (pin "2") (pinfunction "D1+_2") (pintype "passive"))
    )
    (net (code "175") (name "Net-(U5-D1-)") (class "Default")
      (node (ref "J16") (pin "3") (pinfunction "3_3") (pintype "passive"))
      (node (ref "U5") (pin "8") (pinfunction "D1-_8") (pintype "passive"))
    )
    (net (code "176") (name "Net-(U30-P1)") (class "Default")
      (node (ref "C12") (pin "1") (pinfunction "1_1") (pintype "passive"))
      (node (ref "U30") (pin "1") (pinfunction "P1_1") (pintype "passive"))
    )
    (net (code "177") (name "Net-(U30-P2)") (class "Default")
      (node (ref "C14") (pin "1") (pinfunction "1_1") (pintype "passive"))
      (node (ref "U30") (pin "3") (pinfunction "P2_3") (pintype "passive"))
    )
    (net (code "178") (name "Net-(U30-PC)") (class "Default")
      (node (ref "C13") (pin "2") (pinfunction "2_2") (pintype "passive"))
      (node (ref "U30") (pin "5") (pinfunction "PC_5") (pintype "passive"))
    )
    (net (code "179") (name "unconnected-(J1-NC-Pad7)") (class "Default")
      (node (ref "J1") (pin "7") (pinfunction "NC_7") (pintype "passive"))
    )
    (net (code "180") (name "unconnected-(J1-NC-Pad9)") (class "Default")
      (node (ref "J1") (pin "9") (pinfunction "NC_9") (pintype "passive"))
    )
    (net (code "181") (name "unconnected-(J1-SWO{slash}TDO-Pad6)") (class "Default")
      (node (ref "J1") (pin "6") (pinfunction "SWO/TDO_6") (pintype "passive"))
    )
    (net (code "182") (name "unconnected-(J1-TDI-Pad8)") (class "Default")
      (node (ref "J1") (pin "8") (pinfunction "TDI_8") (pintype "passive"))
    )
    (net (code "183") (name "unconnected-(J2-Pad4)") (class "Default")
      (node (ref "J2") (pin "4") (pinfunction "4_4") (pintype "passive"))
    )
    (net (code "184") (name "unconnected-(J2-Pad6)") (class "Default")
      (node (ref "J2") (pin "6") (pinfunction "6_6") (pintype "passive"))
    )
    (net (code "185") (name "unconnected-(J2-Pad8)") (class "Default")
      (node (ref "J2") (pin "8") (pinfunction "8_8") (pintype "passive"))
    )
    (net (code "186") (name "unconnected-(J2-Pad9)") (class "Default")
      (node (ref "J2") (pin "9") (pinfunction "9_9") (pintype "passive"))
    )
    (net (code "187") (name "unconnected-(J2-Pad10)") (class "Default")
      (node (ref "J2") (pin "10") (pinfunction "10_10") (pintype "passive"))
    )
    (net (code "188") (name "unconnected-(J2-Pad11)") (class "Default")
      (node (ref "J2") (pin "11") (pinfunction "11_11") (pintype "passive"))
    )
    (net (code "189") (name "unconnected-(J2-Pad12)") (class "Default")
      (node (ref "J2") (pin "12") (pinfunction "12_12") (pintype "passive"))
    )
    (net (code "190") (name "unconnected-(J2-Pad13)") (class "Default")
      (node (ref "J2") (pin "13") (pinfunction "13_13") (pintype "passive"))
    )
    (net (code "191") (name "unconnected-(J2-Pad15)") (class "Default")
      (node (ref "J2") (pin "15") (pinfunction "15_15") (pintype "passive"))
    )
    (net (code "192") (name "unconnected-(J4-NC-Pad7)") (class "Default")
      (node (ref "J4") (pin "7") (pinfunction "NC_7") (pintype "passive"))
    )
    (net (code "193") (name "unconnected-(J4-NC-Pad9)") (class "Default")
      (node (ref "J4") (pin "9") (pinfunction "NC_9") (pintype "passive"))
    )
    (net (code "194") (name "unconnected-(J4-SWO{slash}TDO-Pad6)") (class "Default")
      (node (ref "J4") (pin "6") (pinfunction "SWO/TDO_6") (pintype "passive"))
    )
    (net (code "195") (name "unconnected-(J4-TDI-Pad8)") (class "Default")
      (node (ref "J4") (pin "8") (pinfunction "TDI_8") (pintype "passive"))
    )
    (net (code "196") (name "unconnected-(J5-Pad1)") (class "Default")
      (node (ref "J5") (pin "1") (pinfunction "1_1") (pintype "passive"))
    )
    (net (code "197") (name "unconnected-(J5-Pad13)") (class "Default")
      (node (ref "J5") (pin "13") (pinfunction "13_13") (pintype "passive"))
    )
    (net (code "198") (name "unconnected-(J5-Pad15)") (class "Default")
      (node (ref "J5") (pin "15") (pinfunction "15_15") (pintype "passive"))
    )
    (net (code "199") (name "unconnected-(J6-CAN1_H-Pad16)") (class "Default")
      (node (ref "J6") (pin "16") (pinfunction "CAN1_H_16") (pintype "passive"))
    )
    (net (code "200") (name "unconnected-(J6-CAN1_L-Pad4)") (class "Default")
      (node (ref "J6") (pin "4") (pinfunction "CAN1_L_4") (pintype "passive"))
    )
    (net (code "201") (name "unconnected-(J6-CAN2_H-Pad18)") (class "Default")
      (node (ref "J6") (pin "18") (pinfunction "CAN2_H_18") (pintype "passive"))
    )
    (net (code "202") (name "unconnected-(J6-CAN2_L-Pad6)") (class "Default")
      (node (ref "J6") (pin "6") (pinfunction "CAN2_L_6") (pintype "passive"))
    )
    (net (code "203") (name "unconnected-(J6-GPI1-Pad24)") (class "Default")
      (node (ref "J6") (pin "24") (pinfunction "GPI1_24") (pintype "passive"))
    )
    (net (code "204") (name "unconnected-(J6-GPO1-Pad11)") (class "Default")
      (node (ref "J6") (pin "11") (pinfunction "GPO1_11") (pintype "passive"))
    )
    (net (code "205") (name "unconnected-(J6-GPO2-Pad12)") (class "Default")
      (node (ref "J6") (pin "12") (pinfunction "GPO2_12") (pintype "passive"))
    )
    (net (code "206") (name "unconnected-(J6-GPO3-Pad23)") (class "Default")
      (node (ref "J6") (pin "23") (pinfunction "GPO3_23") (pintype "passive"))
    )
    (net (code "207") (name "unconnected-(J7-CAN1_H-Pad9)") (class "Default")
      (node (ref "J7") (pin "9") (pinfunction "CAN1_H_9") (pintype "passive"))
    )
    (net (code "208") (name "unconnected-(J7-CAN1_L-Pad2)") (class "Default")
      (node (ref "J7") (pin "2") (pinfunction "CAN1_L_2") (pintype "passive"))
    )
    (net (code "209") (name "unconnected-(J7-REL1_A-Pad7)") (class "Default")
      (node (ref "J7") (pin "7") (pinfunction "REL1_A_7") (pintype "passive"))
    )
    (net (code "210") (name "unconnected-(J7-REL1_B-Pad14)") (class "Default")
      (node (ref "J7") (pin "14") (pinfunction "REL1_B_14") (pintype "passive"))
    )
    (net (code "211") (name "unconnected-(J7-VCC-Pad1)") (class "Default")
      (node (ref "J7") (pin "1") (pinfunction "VCC_1") (pintype "passive"))
    )
    (net (code "212") (name "unconnected-(J15-ID-Pad4)") (class "Default")
      (node (ref "J15") (pin "4") (pinfunction "ID_4") (pintype "passive"))
    )
    (net (code "213") (name "unconnected-(U1-3V3-Pad1)") (class "Default")
      (node (ref "U1") (pin "1") (pinfunction "3V3_1") (pintype "power_in"))
    )
    (net (code "214") (name "unconnected-(U1-3V3-Pad17)") (class "Default")
      (node (ref "U1") (pin "17") (pinfunction "3V3_17") (pintype "power_in"))
    )
    (net (code "215") (name "unconnected-(U1-GPIO2{slash}SDA1-Pad3)") (class "Default")
      (node (ref "U1") (pin "3") (pinfunction "GPIO2/SDA1_3") (pintype "bidirectional"))
    )
    (net (code "216") (name "unconnected-(U1-GPIO3{slash}SCL1-Pad5)") (class "Default")
      (node (ref "U1") (pin "5") (pinfunction "GPIO3/SCL1_5") (pintype "bidirectional"))
    )
    (net (code "217") (name "unconnected-(U1-GPIO4{slash}GPIO_GCKL-Pad7)") (class "Default")
      (node (ref "U1") (pin "7") (pinfunction "GPIO4/GPIO_GCKL_7") (pintype "bidirectional"))
    )
    (net (code "218") (name "unconnected-(U1-GPIO7{slash}~{SPI_CE1}-Pad26)") (class "Default")
      (node (ref "U1") (pin "26") (pinfunction "GPIO7/~{SPI_CE1}_26") (pintype "bidirectional"))
    )
    (net (code "219") (name "unconnected-(U1-GPIO8{slash}~{SPI_CE0}-Pad24)") (class "Default")
      (node (ref "U1") (pin "24") (pinfunction "GPIO8/~{SPI_CE0}_24") (pintype "bidirectional"))
    )
    (net (code "220") (name "unconnected-(U1-GPIO9{slash}SPI_MISO-Pad21)") (class "Default")
      (node (ref "U1") (pin "21") (pinfunction "GPIO9/SPI_MISO_21") (pintype "bidirectional"))
    )
    (net (code "221") (name "unconnected-(U1-GPIO10{slash}SPI_MOSI-Pad19)") (class "Default")
      (node (ref "U1") (pin "19") (pinfunction "GPIO10/SPI_MOSI_19") (pintype "bidirectional"))
    )
    (net (code "222") (name "unconnected-(U1-GPIO11{slash}SPI_SCLK-Pad23)") (class "Default")
      (node (ref "U1") (pin "23") (pinfunction "GPIO11/SPI_SCLK_23") (pintype "bidirectional"))
    )
    (net (code "223") (name "unconnected-(U1-GPIO12-Pad32)") (class "Default")
      (node (ref "U1") (pin "32") (pinfunction "GPIO12_32") (pintype "bidirectional"))
    )
    (net (code "224") (name "unconnected-(U1-GPIO13-Pad33)") (class "Default")
      (node (ref "U1") (pin "33") (pinfunction "GPIO13_33") (pintype "bidirectional"))
    )
    (net (code "225") (name "unconnected-(U1-GPIO16-Pad36)") (class "Default")
      (node (ref "U1") (pin "36") (pinfunction "GPIO16_36") (pintype "bidirectional"))
    )
    (net (code "226") (name "unconnected-(U1-GPIO17{slash}GPIO_GEN0-Pad11)") (class "Default")
      (node (ref "U1") (pin "11") (pinfunction "GPIO17/GPIO_GEN0_11") (pintype "bidirectional"))
    )
    (net (code "227") (name "unconnected-(U1-GPIO18{slash}GPIO_GEN1-Pad12)") (class "Default")
      (node (ref "U1") (pin "12") (pinfunction "GPIO18/GPIO_GEN1_12") (pintype "bidirectional"))
    )
    (net (code "228") (name "unconnected-(U1-GPIO19-Pad35)") (class "Default")
      (node (ref "U1") (pin "35") (pinfunction "GPIO19_35") (pintype "bidirectional"))
    )
    (net (code "229") (name "unconnected-(U1-GPIO20-Pad38)") (class "Default")
      (node (ref "U1") (pin "38") (pinfunction "GPIO20_38") (pintype "bidirectional"))
    )
    (net (code "230") (name "unconnected-(U1-GPIO21-Pad40)") (class "Default")
      (node (ref "U1") (pin "40") (pinfunction "GPIO21_40") (pintype "bidirectional"))
    )
    (net (code "231") (name "unconnected-(U1-GPIO22{slash}GPIO_GEN3-Pad15)") (class "Default")
      (node (ref "U1") (pin "15") (pinfunction "GPIO22/GPIO_GEN3_15") (pintype "bidirectional"))
    )
    (net (code "232") (name "unconnected-(U1-GPIO23{slash}GPIO_GEN4-Pad16)") (class "Default")
      (node (ref "U1") (pin "16") (pinfunction "GPIO23/GPIO_GEN4_16") (pintype "bidirectional"))
    )
    (net (code "233") (name "unconnected-(U1-GPIO24{slash}GPIO_GEN5-Pad18)") (class "Default")
      (node (ref "U1") (pin "18") (pinfunction "GPIO24/GPIO_GEN5_18") (pintype "bidirectional"))
    )
    (net (code "234") (name "unconnected-(U1-GPIO25{slash}GPIO_GEN6-Pad22)") (class "Default")
      (node (ref "U1") (pin "22") (pinfunction "GPIO25/GPIO_GEN6_22") (pintype "bidirectional"))
    )
    (net (code "235") (name "unconnected-(U1-GPIO26-Pad37)") (class "Default")
      (node (ref "U1") (pin "37") (pinfunction "GPIO26_37") (pintype "bidirectional"))
    )
    (net (code "236") (name "unconnected-(U1-GPIO27{slash}GPIO_GEN2-Pad13)") (class "Default")
      (node (ref "U1") (pin "13") (pinfunction "GPIO27/GPIO_GEN2_13") (pintype "bidirectional"))
    )
    (net (code "237") (name "unconnected-(U1-ID_SC-Pad28)") (class "Default")
      (node (ref "U1") (pin "28") (pinfunction "ID_SC_28") (pintype "bidirectional"))
    )
    (net (code "238") (name "unconnected-(U1-ID_SD-Pad27)") (class "Default")
      (node (ref "U1") (pin "27") (pinfunction "ID_SD_27") (pintype "bidirectional"))
    )
    (net (code "239") (name "unconnected-(U1-TR00-Pad42)") (class "Default")
      (node (ref "U1") (pin "42") (pinfunction "TR00_42") (pintype "bidirectional"))
    )
    (net (code "240") (name "unconnected-(U1-TR01-Pad41)") (class "Default")
      (node (ref "U1") (pin "41") (pinfunction "TR01_41") (pintype "bidirectional"))
    )
    (net (code "241") (name "unconnected-(U1-TR02-Pad44)") (class "Default")
      (node (ref "U1") (pin "44") (pinfunction "TR02_44") (pintype "bidirectional"))
    )
    (net (code "242") (name "unconnected-(U1-TR03-Pad43)") (class "Default")
      (node (ref "U1") (pin "43") (pinfunction "TR03_43") (pintype "bidirectional"))
    )
    (net (code "243") (name "unconnected-(U4-FLG-Pad4)") (class "Default")
      (node (ref "U4") (pin "4") (pinfunction "FLG_4") (pintype "passive"))
    )
    (net (code "244") (name "unconnected-(U5-D2+-Pad3)") (class "Default")
      (node (ref "U5") (pin "3") (pinfunction "D2+_3") (pintype "passive"))
    )
    (net (code "245") (name "unconnected-(U5-D2--Pad7)") (class "Default")
      (node (ref "U5") (pin "7") (pinfunction "D2-_7") (pintype "passive"))
    )
  )
)
